# bme_rfm95.net
KiCad netlist of a schematic drawn in Altium Designer
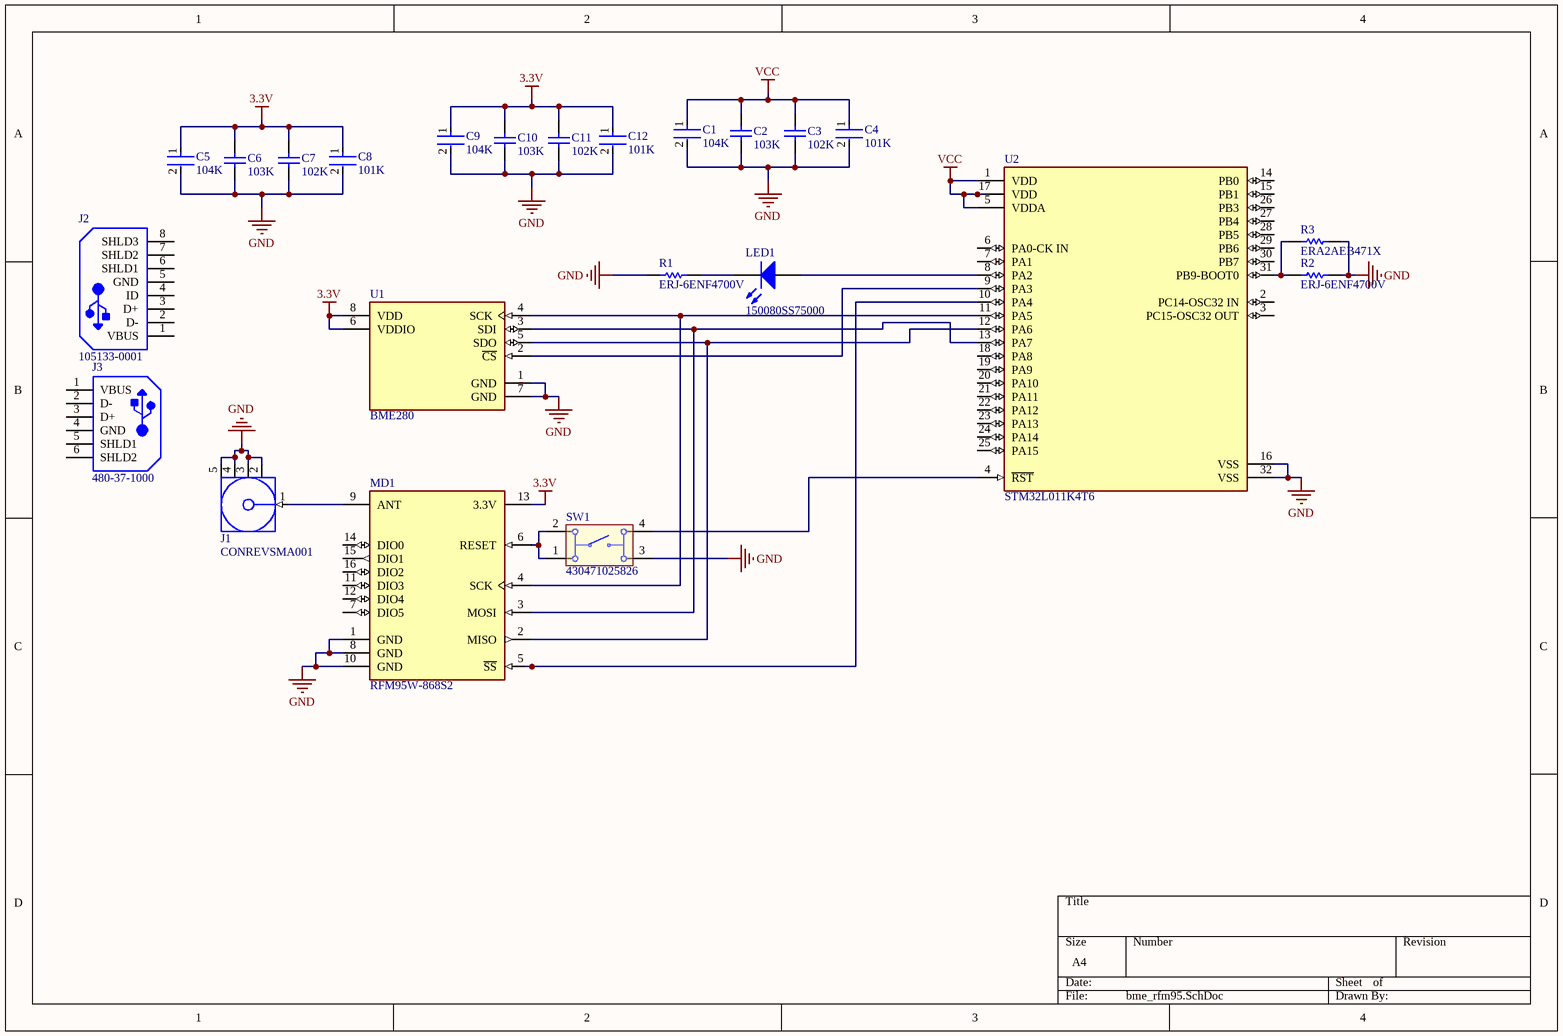
[diagram p0: bme_rfm95.SchDoc]

(export (version "E")
  (design (tool "Eeschema 10.0.6"))
  (components
    (comp (ref "C1")
      (value "104K")
      (footprint "FP-C0805C-DN-MFG")
      (description "CAP CER 0.1UF 50V X7R 0805")
      (fields
        (field (name "MANUFACTURER PART NUMBER") "C0805C104K5RACTU")
        (field (name "MANUFACTURER") "KEMET")
      )
      (libsource (lib "Altium Content Vault") (part "b4654b650e69147ec39a6b967a45e02"))
    )
    (comp (ref "C2")
      (value "103K")
      (footprint "CAPC2013X100X50NL20T25")
      (fields (field (name "PART NUMBER") "C0805F103K5RACTU") (field (name "MANUFACTURER") "Kemet"))
      (libsource (lib "Altium Content Vault") (part "CAP"))
    )
    (comp (ref "C3")
      (value "102K")
      (footprint "CAPC2013X100X50LL20T25")
      (fields (field (name "MANUFACTURER") "Kemet") (field (name "PART NUMBER") "C0805F102K1RACAUTO"))
      (libsource (lib "Altium Content Vault") (part "CAP"))
    )
    (comp (ref "C4")
      (value "101K")
      (footprint "FP-C0805C-DN-MFG")
      (description "C0805 100 pF X7R 30ppm/°C 10.00% 50 V")
      (fields
        (field (name "MANUFACTURER PART NUMBER") "C0805C101K5RAC")
        (field (name "MANUFACTURER") "KEMET")
      )
      (libsource (lib "Altium Content Vault") (part "b4654b650e69147ec39a6b967a45e02"))
    )
    (comp (ref "C5")
      (value "104K")
      (footprint "FP-C0805C-DN-MFG")
      (description "CAP CER 0.1UF 50V X7R 0805")
      (fields
        (field (name "MANUFACTURER PART NUMBER") "C0805C104K5RACTU")
        (field (name "MANUFACTURER") "KEMET")
      )
      (libsource (lib "Altium Content Vault") (part "b4654b650e69147ec39a6b967a45e02"))
    )
    (comp (ref "C6")
      (value "103K")
      (footprint "CAPC2013X100X50NL20T25")
      (fields (field (name "PART NUMBER") "C0805F103K5RACTU") (field (name "MANUFACTURER") "Kemet"))
      (libsource (lib "Altium Content Vault") (part "CAP"))
    )
    (comp (ref "C7")
      (value "102K")
      (footprint "CAPC2013X100X50LL20T25")
      (fields (field (name "MANUFACTURER") "Kemet") (field (name "PART NUMBER") "C0805F102K1RACAUTO"))
      (libsource (lib "Altium Content Vault") (part "CAP"))
    )
    (comp (ref "C8")
      (value "101K")
      (footprint "FP-C0805C-DN-MFG")
      (description "C0805 100 pF X7R 30ppm/°C 10.00% 50 V")
      (fields
        (field (name "MANUFACTURER PART NUMBER") "C0805C101K5RAC")
        (field (name "MANUFACTURER") "KEMET")
      )
      (libsource (lib "Altium Content Vault") (part "b4654b650e69147ec39a6b967a45e02"))
    )
    (comp (ref "C9")
      (value "104K")
      (footprint "FP-C0805C-DN-MFG")
      (description "CAP CER 0.1UF 50V X7R 0805")
      (fields
        (field (name "MANUFACTURER PART NUMBER") "C0805C104K5RACTU")
        (field (name "MANUFACTURER") "KEMET")
      )
      (libsource (lib "Altium Content Vault") (part "b4654b650e69147ec39a6b967a45e02"))
    )
    (comp (ref "C10")
      (value "103K")
      (footprint "CAPC2013X100X50NL20T25")
      (fields (field (name "PART NUMBER") "C0805F103K5RACTU") (field (name "MANUFACTURER") "Kemet"))
      (libsource (lib "Altium Content Vault") (part "CAP"))
    )
    (comp (ref "C11")
      (value "102K")
      (footprint "CAPC2013X100X50LL20T25")
      (fields (field (name "MANUFACTURER") "Kemet") (field (name "PART NUMBER") "C0805F102K1RACAUTO"))
      (libsource (lib "Altium Content Vault") (part "CAP"))
    )
    (comp (ref "C12")
      (value "101K")
      (footprint "FP-C0805C-DN-MFG")
      (description "C0805 100 pF X7R 30ppm/°C 10.00% 50 V")
      (fields
        (field (name "MANUFACTURER PART NUMBER") "C0805C101K5RAC")
        (field (name "MANUFACTURER") "KEMET")
      )
      (libsource (lib "Altium Content Vault") (part "b4654b650e69147ec39a6b967a45e02"))
    )
    (comp (ref "J1")
      (value "CONREVSMA001")
      (footprint "CON-REVSMA")
      (description "RP-SMA Female PCB Mount Connector, Thru-Hole")
      (libsource (lib "Altium Content Vault") (part "CN-1P-F-RF5"))
    )
    (comp (ref "J2")
      (value "105133-0001")
      (footprint "MOLX-105133-0001_V")
      (description "Micro-USB B Receptacle, Vertical, -30 to 85 degC, 5-Pin SMD, RoHS, Tape and Reel")
      (fields (field (name "MANUFACTURER") "Molex"))
      (libsource (lib "Altium Content Vault") (part "USB-5-3SHLD"))
    )
    (comp (ref "J3")
      (value "480-37-1000")
      (footprint "MOLX-480-37-1000_V")
      (fields (field (name "TOLERANCE") "1%"))
      (libsource (lib "Altium Content Vault") (part "USB-4-2SHLD"))
    )
    (comp (ref "LED1")
      (value "150080SS75000")
      (footprint "0805_A")
      (description "SMD mono-color Chip LED, WL-SMCW, Super Red")
      (fields (field (name "MANUFACTURER") "Wuerth Elektronik"))
      (libsource (lib "Altium Content Vault") (part "WE-LED_K1A2-2"))
    )
    (comp (ref "MD1")
      (value "RFM95W-868S2")
      (footprint "FP-RFM95W-868S2-MFG")
      (description "RX TXRX MODULE ISM < 1GHZ SMD")
      (libsource (lib "Altium Content Vault") (part "17626aa6fba47fab2b206b7c140802e"))
    )
    (comp (ref "R1")
      (value "ERJ-6ENF4700V")
      (footprint "RESC2013X70X40LL20T20")
      (description "Chip Resistor, 470 Ohm, +/- 1%, 0.125 W, -55 to 155 degC, 0805 (2012 Metric), RoHS, Tape and Reel")
      (fields (field (name "MANUFACTURER") "Panasonic"))
      (libsource (lib "Altium Content Vault") (part "RES-2"))
    )
    (comp (ref "R2")
      (value "ERJ-6ENF4700V")
      (footprint "RESC2013X70X40LL20T20")
      (description "Chip Resistor, 470 Ohm, +/- 1%, 0.125 W, -55 to 155 degC, 0805 (2012 Metric), RoHS, Tape and Reel")
      (fields (field (name "MANUFACTURER") "Panasonic"))
      (libsource (lib "Altium Content Vault") (part "RES-2"))
    )
    (comp (ref "R3")
      (value "ERA2AEB471X")
      (footprint "RESC1005X40X25ML10T10")
      (fields (field (name "MANUFACTURER") "Panasonic"))
      (libsource (lib "Altium Content Vault") (part "RES"))
    )
    (comp (ref "SW1")
      (value "430471025826")
      (footprint "430471025826")
      (description "WS-TASV SMD Tact Switch 6X6 mm")
      (fields (field (name "MANUFACTURER") "Wuerth Elektronik"))
      (libsource (lib "Altium Content Vault") (part "WE-TACT-SW-4_A"))
    )
    (comp (ref "U1")
      (value "BME280")
      (footprint "FP-BME280-MFG")
      (description "SENSOR PRESSURE HUMIDITY TEMP")
      (libsource (lib "Altium Content Vault") (part "d58e2f6669bc67e6a2bc6a28610ca79"))
    )
    (comp (ref "U2")
      (value "STM32L011K4T6")
      (footprint "FP-LQFP32-5V-MFG")
      (description "IC MCU 32BIT 16KB FLASH 32LQFP")
      (fields
        (field (name "MANUFACTURER") "STMicroelectronics")
        (field (name "OCTOPART") "https://octopart.com/stm32l011k4t6-stmicroelectronics-71108062")
      )
      (libsource (lib "Altium Content Vault") (part "3cbf9028c7ade503566d0a55c35e94d"))
    )
  )
  (nets
    (net (code "1") (name "3.3V") (class "Default")
      (node (ref "C10") (pin "2") (pinfunction "2_2") (pintype "passive"))
      (node (ref "C11") (pin "2") (pinfunction "2_2") (pintype "passive"))
      (node (ref "C12") (pin "1") (pinfunction "1_1") (pintype "passive"))
      (node (ref "C5") (pin "1") (pinfunction "1_1") (pintype "passive"))
      (node (ref "C6") (pin "2") (pinfunction "2_2") (pintype "passive"))
      (node (ref "C7") (pin "2") (pinfunction "2_2") (pintype "passive"))
      (node (ref "C8") (pin "1") (pinfunction "1_1") (pintype "passive"))
      (node (ref "C9") (pin "1") (pinfunction "1_1") (pintype "passive"))
      (node (ref "MD1") (pin "13") (pinfunction "3.3V_13") (pintype "power_in"))
      (node (ref "U1") (pin "6") (pinfunction "VDDIO_6") (pintype "power_in"))
      (node (ref "U1") (pin "8") (pinfunction "VDD_8") (pintype "power_in"))
    )
    (net (code "2") (name "GND") (class "Default")
      (node (ref "C1") (pin "2") (pinfunction "2_2") (pintype "passive"))
      (node (ref "C10") (pin "1") (pinfunction "1_1") (pintype "passive"))
      (node (ref "C11") (pin "1") (pinfunction "1_1") (pintype "passive"))
      (node (ref "C12") (pin "2") (pinfunction "2_2") (pintype "passive"))
      (node (ref "C2") (pin "1") (pinfunction "1_1") (pintype "passive"))
      (node (ref "C3") (pin "1") (pinfunction "1_1") (pintype "passive"))
      (node (ref "C4") (pin "2") (pinfunction "2_2") (pintype "passive"))
      (node (ref "C5") (pin "2") (pinfunction "2_2") (pintype "passive"))
      (node (ref "C6") (pin "1") (pinfunction "1_1") (pintype "passive"))
      (node (ref "C7") (pin "1") (pinfunction "1_1") (pintype "passive"))
      (node (ref "C8") (pin "2") (pinfunction "2_2") (pintype "passive"))
      (node (ref "C9") (pin "2") (pinfunction "2_2") (pintype "passive"))
      (node (ref "J1") (pin "2") (pinfunction "GND_2") (pintype "power_in"))
      (node (ref "J1") (pin "3") (pinfunction "GND_3") (pintype "power_in"))
      (node (ref "J1") (pin "4") (pinfunction "GND_4") (pintype "power_in"))
      (node (ref "J1") (pin "5") (pinfunction "GND_5") (pintype "power_in"))
      (node (ref "MD1") (pin "1") (pinfunction "GND_1") (pintype "power_in"))
      (node (ref "MD1") (pin "10") (pinfunction "GND_10") (pintype "power_in"))
      (node (ref "MD1") (pin "8") (pinfunction "GND_8") (pintype "power_in"))
      (node (ref "R1") (pin "1") (pinfunction "1_1") (pintype "passive"))
      (node (ref "R2") (pin "2") (pinfunction "2_2") (pintype "passive"))
      (node (ref "R3") (pin "2") (pinfunction "2_2") (pintype "passive"))
      (node (ref "SW1") (pin "3") (pinfunction "3_3") (pintype "passive"))
      (node (ref "U1") (pin "1") (pinfunction "GND_1") (pintype "power_in"))
      (node (ref "U1") (pin "7") (pinfunction "GND_7") (pintype "power_in"))
      (node (ref "U2") (pin "16") (pinfunction "VSS_16") (pintype "power_in"))
      (node (ref "U2") (pin "32") (pinfunction "VSS_32") (pintype "power_in"))
    )
    (net (code "3") (name "Net-(J1-Signal)") (class "Default")
      (node (ref "J1") (pin "1") (pinfunction "Signal_1") (pintype "input"))
      (node (ref "MD1") (pin "9") (pinfunction "ANT_9") (pintype "passive"))
    )
    (net (code "4") (name "Net-(LED1-A)") (class "Default")
      (node (ref "LED1") (pin "2") (pinfunction "A_2") (pintype "passive"))
      (node (ref "U2") (pin "8") (pinfunction "PA2_8") (pintype "bidirectional"))
    )
    (net (code "5") (name "Net-(LED1-K)") (class "Default")
      (node (ref "LED1") (pin "1") (pinfunction "K_1") (pintype "passive"))
      (node (ref "R1") (pin "2") (pinfunction "2_2") (pintype "passive"))
    )
    (net (code "6") (name "Net-(MD1-MISO)") (class "Default")
      (node (ref "MD1") (pin "2") (pinfunction "MISO_2") (pintype "output"))
      (node (ref "U1") (pin "5") (pinfunction "SDO_5") (pintype "bidirectional"))
      (node (ref "U2") (pin "12") (pinfunction "PA6_12") (pintype "bidirectional"))
    )
    (net (code "7") (name "Net-(MD1-MOSI)") (class "Default")
      (node (ref "MD1") (pin "3") (pinfunction "MOSI_3") (pintype "input"))
      (node (ref "U1") (pin "3") (pinfunction "SDI_3") (pintype "bidirectional"))
      (node (ref "U2") (pin "13") (pinfunction "PA7_13") (pintype "bidirectional"))
    )
    (net (code "8") (name "Net-(MD1-RESET)") (class "Default")
      (node (ref "MD1") (pin "6") (pinfunction "RESET_6") (pintype "input"))
      (node (ref "SW1") (pin "1") (pinfunction "1_1") (pintype "passive"))
      (node (ref "SW1") (pin "2") (pinfunction "2_2") (pintype "passive"))
    )
    (net (code "9") (name "Net-(MD1-SCK)") (class "Default")
      (node (ref "MD1") (pin "4") (pinfunction "SCK_4") (pintype "input"))
      (node (ref "U1") (pin "4") (pinfunction "SCK_4") (pintype "input"))
      (node (ref "U2") (pin "11") (pinfunction "PA5_11") (pintype "bidirectional"))
    )
    (net (code "10") (name "Net-(MD1-~{SS})") (class "Default")
      (node (ref "MD1") (pin "5") (pinfunction "~{SS}_5") (pintype "input"))
      (node (ref "U2") (pin "10") (pinfunction "PA4_10") (pintype "bidirectional"))
    )
    (net (code "11") (name "Net-(U1-~{CS})") (class "Default")
      (node (ref "U1") (pin "2") (pinfunction "~{CS}_2") (pintype "input"))
      (node (ref "U2") (pin "9") (pinfunction "PA3_9") (pintype "bidirectional"))
    )
    (net (code "12") (name "Net-(U2-PB9-BOOT0)") (class "Default")
      (node (ref "R2") (pin "1") (pinfunction "1_1") (pintype "passive"))
      (node (ref "R3") (pin "1") (pinfunction "1_1") (pintype "passive"))
      (node (ref "U2") (pin "31") (pinfunction "PB9-BOOT0_31") (pintype "bidirectional"))
    )
    (net (code "13") (name "Net-(U2-~{RST})") (class "Default")
      (node (ref "SW1") (pin "4") (pinfunction "4_4") (pintype "passive"))
      (node (ref "U2") (pin "4") (pinfunction "~{RST}_4") (pintype "input"))
    )
    (net (code "14") (name "VCC") (class "Default")
      (node (ref "C1") (pin "1") (pinfunction "1_1") (pintype "passive"))
      (node (ref "C2") (pin "2") (pinfunction "2_2") (pintype "passive"))
      (node (ref "C3") (pin "2") (pinfunction "2_2") (pintype "passive"))
      (node (ref "C4") (pin "1") (pinfunction "1_1") (pintype "passive"))
      (node (ref "U2") (pin "1") (pinfunction "VDD_1") (pintype "power_in"))
      (node (ref "U2") (pin "17") (pinfunction "VDD_17") (pintype "power_in"))
      (node (ref "U2") (pin "5") (pinfunction "VDDA_5") (pintype "power_in"))
    )
    (net (code "15") (name "unconnected-(J2-D+-Pad3)") (class "Default")
      (node (ref "J2") (pin "3") (pinfunction "D+_3") (pintype "passive"))
    )
    (net (code "16") (name "unconnected-(J2-D--Pad2)") (class "Default")
      (node (ref "J2") (pin "2") (pinfunction "D-_2") (pintype "passive"))
    )
    (net (code "17") (name "unconnected-(J2-GND-Pad5)") (class "Default")
      (node (ref "J2") (pin "5") (pinfunction "GND_5") (pintype "passive"))
    )
    (net (code "18") (name "unconnected-(J2-ID-Pad4)") (class "Default")
      (node (ref "J2") (pin "4") (pinfunction "ID_4") (pintype "passive"))
    )
    (net (code "19") (name "unconnected-(J2-SHLD1-Pad6)") (class "Default")
      (node (ref "J2") (pin "6") (pinfunction "SHLD1_6") (pintype "passive"))
    )
    (net (code "20") (name "unconnected-(J2-SHLD2-Pad7)") (class "Default")
      (node (ref "J2") (pin "7") (pinfunction "SHLD2_7") (pintype "passive"))
    )
    (net (code "21") (name "unconnected-(J2-SHLD3-Pad8)") (class "Default")
      (node (ref "J2") (pin "8") (pinfunction "SHLD3_8") (pintype "passive"))
    )
    (net (code "22") (name "unconnected-(J2-VBUS-Pad1)") (class "Default")
      (node (ref "J2") (pin "1") (pinfunction "VBUS_1") (pintype "passive"))
    )
    (net (code "23") (name "unconnected-(J3-D+-Pad3)") (class "Default")
      (node (ref "J3") (pin "3") (pinfunction "D+_3") (pintype "passive"))
    )
    (net (code "24") (name "unconnected-(J3-D--Pad2)") (class "Default")
      (node (ref "J3") (pin "2") (pinfunction "D-_2") (pintype "passive"))
    )
    (net (code "25") (name "unconnected-(J3-GND-Pad4)") (class "Default")
      (node (ref "J3") (pin "4") (pinfunction "GND_4") (pintype "passive"))
    )
    (net (code "26") (name "unconnected-(J3-SHLD1-Pad5)") (class "Default")
      (node (ref "J3") (pin "5") (pinfunction "SHLD1_5") (pintype "passive"))
    )
    (net (code "27") (name "unconnected-(J3-SHLD2-Pad6)") (class "Default")
      (node (ref "J3") (pin "6") (pinfunction "SHLD2_6") (pintype "passive"))
    )
    (net (code "28") (name "unconnected-(J3-VBUS-Pad1)") (class "Default")
      (node (ref "J3") (pin "1") (pinfunction "VBUS_1") (pintype "passive"))
    )
    (net (code "29") (name "unconnected-(MD1-DIO0-Pad14)") (class "Default")
      (node (ref "MD1") (pin "14") (pinfunction "DIO0_14") (pintype "bidirectional"))
    )
    (net (code "30") (name "unconnected-(MD1-DIO1-Pad15)") (class "Default")
      (node (ref "MD1") (pin "15") (pinfunction "DIO1_15") (pintype "output"))
    )
    (net (code "31") (name "unconnected-(MD1-DIO2-Pad16)") (class "Default")
      (node (ref "MD1") (pin "16") (pinfunction "DIO2_16") (pintype "bidirectional"))
    )
    (net (code "32") (name "unconnected-(MD1-DIO3-Pad11)") (class "Default")
      (node (ref "MD1") (pin "11") (pinfunction "DIO3_11") (pintype "bidirectional"))
    )
    (net (code "33") (name "unconnected-(MD1-DIO4-Pad12)") (class "Default")
      (node (ref "MD1") (pin "12") (pinfunction "DIO4_12") (pintype "bidirectional"))
    )
    (net (code "34") (name "unconnected-(MD1-DIO5-Pad7)") (class "Default")
      (node (ref "MD1") (pin "7") (pinfunction "DIO5_7") (pintype "bidirectional"))
    )
    (net (code "35") (name "unconnected-(U2-PA0-CK_IN-Pad6)") (class "Default")
      (node (ref "U2") (pin "6") (pinfunction "PA0-CK_IN_6") (pintype "bidirectional"))
    )
    (net (code "36") (name "unconnected-(U2-PA1-Pad7)") (class "Default")
      (node (ref "U2") (pin "7") (pinfunction "PA1_7") (pintype "bidirectional"))
    )
    (net (code "37") (name "unconnected-(U2-PA8-Pad18)") (class "Default")
      (node (ref "U2") (pin "18") (pinfunction "PA8_18") (pintype "bidirectional"))
    )
    (net (code "38") (name "unconnected-(U2-PA9-Pad19)") (class "Default")
      (node (ref "U2") (pin "19") (pinfunction "PA9_19") (pintype "bidirectional"))
    )
    (net (code "39") (name "unconnected-(U2-PA10-Pad20)") (class "Default")
      (node (ref "U2") (pin "20") (pinfunction "PA10_20") (pintype "bidirectional"))
    )
    (net (code "40") (name "unconnected-(U2-PA11-Pad21)") (class "Default")
      (node (ref "U2") (pin "21") (pinfunction "PA11_21") (pintype "bidirectional"))
    )
    (net (code "41") (name "unconnected-(U2-PA12-Pad22)") (class "Default")
      (node (ref "U2") (pin "22") (pinfunction "PA12_22") (pintype "bidirectional"))
    )
    (net (code "42") (name "unconnected-(U2-PA13-Pad23)") (class "Default")
      (node (ref "U2") (pin "23") (pinfunction "PA13_23") (pintype "bidirectional"))
    )
    (net (code "43") (name "unconnected-(U2-PA14-Pad24)") (class "Default")
      (node (ref "U2") (pin "24") (pinfunction "PA14_24") (pintype "bidirectional"))
    )
    (net (code "44") (name "unconnected-(U2-PA15-Pad25)") (class "Default")
      (node (ref "U2") (pin "25") (pinfunction "PA15_25") (pintype "bidirectional"))
    )
    (net (code "45") (name "unconnected-(U2-PB0-Pad14)") (class "Default")
      (node (ref "U2") (pin "14") (pinfunction "PB0_14") (pintype "bidirectional"))
    )
    (net (code "46") (name "unconnected-(U2-PB1-Pad15)") (class "Default")
      (node (ref "U2") (pin "15") (pinfunction "PB1_15") (pintype "bidirectional"))
    )
    (net (code "47") (name "unconnected-(U2-PB3-Pad26)") (class "Default")
      (node (ref "U2") (pin "26") (pinfunction "PB3_26") (pintype "bidirectional"))
    )
    (net (code "48") (name "unconnected-(U2-PB4-Pad27)") (class "Default")
      (node (ref "U2") (pin "27") (pinfunction "PB4_27") (pintype "bidirectional"))
    )
    (net (code "49") (name "unconnected-(U2-PB5-Pad28)") (class "Default")
      (node (ref "U2") (pin "28") (pinfunction "PB5_28") (pintype "bidirectional"))
    )
    (net (code "50") (name "unconnected-(U2-PB6-Pad29)") (class "Default")
      (node (ref "U2") (pin "29") (pinfunction "PB6_29") (pintype "bidirectional"))
    )
    (net (code "51") (name "unconnected-(U2-PB7-Pad30)") (class "Default")
      (node (ref "U2") (pin "30") (pinfunction "PB7_30") (pintype "bidirectional"))
    )
    (net (code "52") (name "unconnected-(U2-PC14-OSC32_IN-Pad2)") (class "Default")
      (node (ref "U2") (pin "2") (pinfunction "PC14-OSC32_IN_2") (pintype "bidirectional"))
    )
    (net (code "53") (name "unconnected-(U2-PC15-OSC32_OUT-Pad3)") (class "Default")
      (node (ref "U2") (pin "3") (pinfunction "PC15-OSC32_OUT_3") (pintype "bidirectional"))
    )
  )
)
